# FubarinoMini_v13.net
KiCad netlist of a schematic drawn in EAGLE
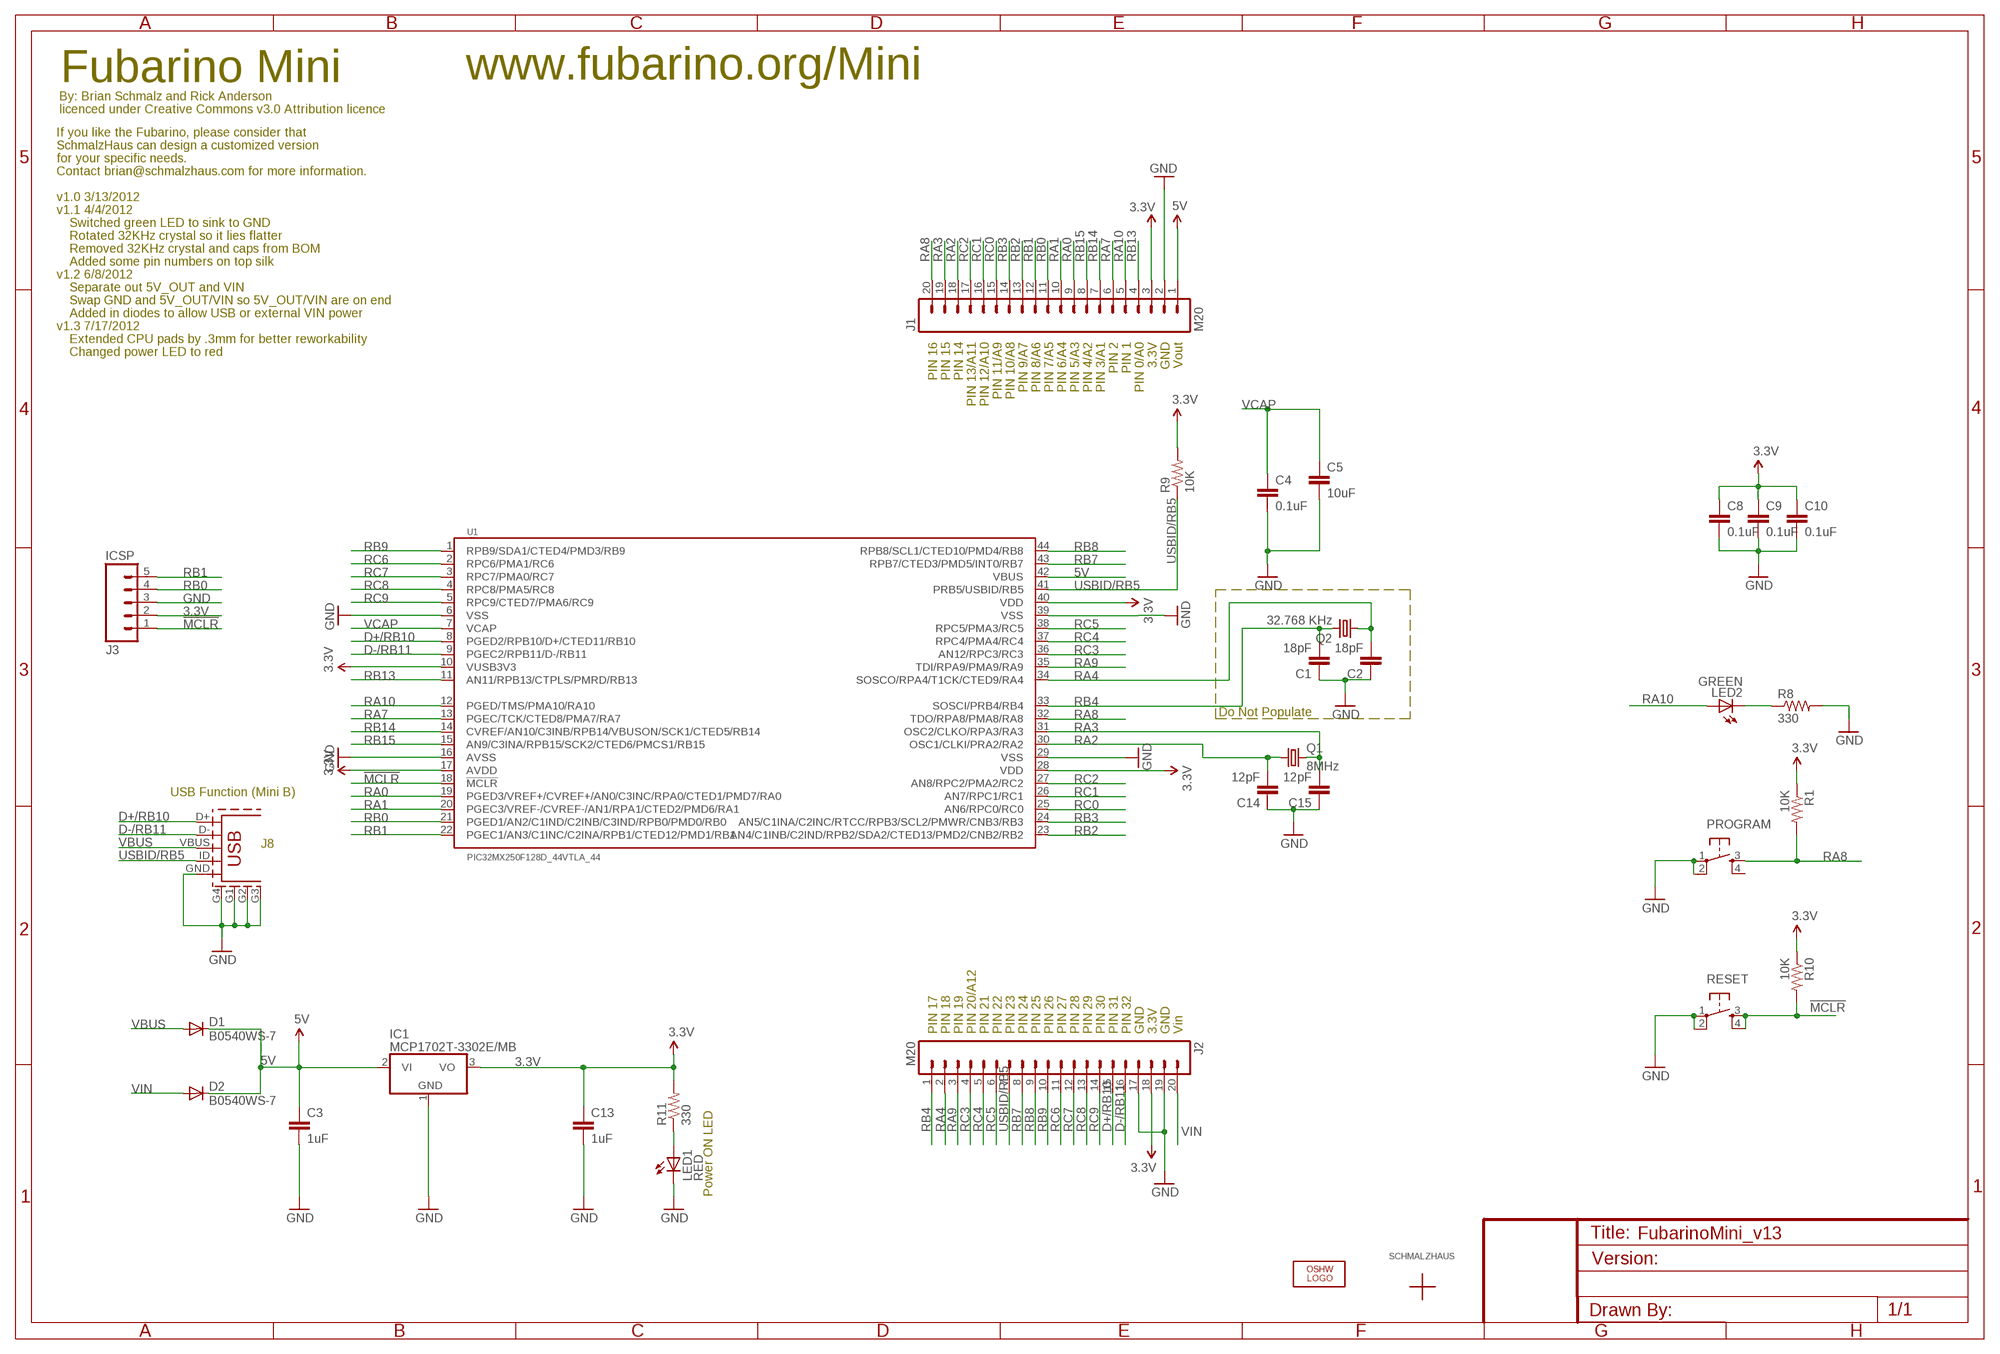
[diagram p0: schematic, sheet 1]

(export (version "E")
  (design (tool "Eeschema 10.0.6"))
  (components
    (comp (ref "C1")
      (value "18pF")
      (footprint "eagle-import:0603-CAP")
      (libsource (lib "eagle-import") (part "SparkFun_CAP0603-CAP"))
    )
    (comp (ref "C2")
      (value "18pF")
      (footprint "eagle-import:0603-CAP")
      (libsource (lib "eagle-import") (part "SparkFun_CAP0603-CAP"))
    )
    (comp (ref "C3")
      (value "1uF")
      (footprint "eagle-import:0603-CAP")
      (libsource (lib "eagle-import") (part "SparkFun_CAP0603-CAP"))
    )
    (comp (ref "C4")
      (value "0.1uF")
      (footprint "eagle-import:0603-CAP")
      (libsource (lib "eagle-import") (part "SparkFun_CAP0603-CAP"))
    )
    (comp (ref "C5")
      (value "10uF")
      (footprint "eagle-import:0805")
      (libsource (lib "eagle-import") (part "CAP0805"))
    )
    (comp (ref "C8")
      (value "0.1uF")
      (footprint "eagle-import:0603-CAP")
      (libsource (lib "eagle-import") (part "SparkFun_CAP0603-CAP"))
    )
    (comp (ref "C9")
      (value "0.1uF")
      (footprint "eagle-import:0603-CAP")
      (libsource (lib "eagle-import") (part "SparkFun_CAP0603-CAP"))
    )
    (comp (ref "C10")
      (value "0.1uF")
      (footprint "eagle-import:0603")
      (libsource (lib "eagle-import") (part "CAP0603"))
    )
    (comp (ref "C13")
      (value "1uF")
      (footprint "eagle-import:0603")
      (libsource (lib "eagle-import") (part "CAP0603"))
    )
    (comp (ref "C14")
      (value "12pF")
      (footprint "eagle-import:0603-CAP")
      (libsource (lib "eagle-import") (part "SparkFun_CAP0603-CAP"))
    )
    (comp (ref "C15")
      (value "12pF")
      (footprint "eagle-import:0603-CAP")
      (libsource (lib "eagle-import") (part "SparkFun_CAP0603-CAP"))
    )
    (comp (ref "D1")
      (value "B0540WS-7")
      (footprint "eagle-import:SOD-323")
      (libsource (lib "eagle-import") (part "DIODESOD"))
    )
    (comp (ref "D2")
      (value "B0540WS-7")
      (footprint "eagle-import:SOD-323")
      (libsource (lib "eagle-import") (part "DIODESOD"))
    )
    (comp (ref "IC1")
      (value "MCP1702T-3302E/MB")
      (footprint "eagle-import:SOT89")
      (libsource (lib "eagle-import") (part "MCP1703MB33"))
    )
    (comp (ref "ICSP")
      (value "J3")
      (footprint "eagle-import:1X05_NOSILK")
      (libsource (lib "eagle-import") (part "M05NOSLILK"))
    )
    (comp (ref "J1")
      (value "M20")
      (footprint "eagle-import:1X20_NO_PIN1")
      (libsource (lib "eagle-import") (part "M20"))
    )
    (comp (ref "J2")
      (value "M20")
      (footprint "eagle-import:1X20_NO_PIN1")
      (libsource (lib "eagle-import") (part "M20"))
    )
    (comp (ref "J8")
      (value "USB_5PIN")
      (footprint "eagle-import:USB-MINIB")
      (libsource (lib "eagle-import") (part "USB_5PIN"))
    )
    (comp (ref "LED1")
      (value "RED")
      (footprint "eagle-import:LED-0603")
      (libsource (lib "eagle-import") (part "LED0603"))
    )
    (comp (ref "LED2")
      (value "GREEN")
      (footprint "eagle-import:LED-0603")
      (libsource (lib "eagle-import") (part "LED0603"))
    )
    (comp (ref "LOGO1")
      (value "OSHW_LOGO_8MILX0070-NT")
      (footprint "eagle-import:OSHW_8X70_NOTEXT")
      (libsource (lib "eagle-import") (part "OSHW_LOGO_8MILX0070-NT"))
    )
    (comp (ref "PROGRAM")
      (value "TAC_SWITCHSND")
      (footprint "eagle-import:TACTILE_SWITCH_SMD")
      (libsource (lib "eagle-import") (part "TAC_SWITCHSND"))
    )
    (comp (ref "Q1")
      (value "8MHz")
      (footprint "eagle-import:NX5032_5MM_3.2MM_CRYSTAL")
      (libsource (lib "eagle-import") (part "CRYSTALNX5032"))
    )
    (comp (ref "Q2")
      (value "32.768 KHz")
      (footprint "eagle-import:TC26H")
      (libsource (lib "eagle-import") (part "CRYSTALTC26H"))
    )
    (comp (ref "R1")
      (value "10K")
      (footprint "eagle-import:0603-RES")
      (libsource (lib "eagle-import") (part "RESISTOR0603-RES"))
    )
    (comp (ref "R8")
      (value "330")
      (footprint "eagle-import:0603-RES")
      (libsource (lib "eagle-import") (part "RESISTOR0603-RES"))
    )
    (comp (ref "R9")
      (value "10K")
      (footprint "eagle-import:0603-RES")
      (libsource (lib "eagle-import") (part "RESISTOR0603-RES"))
    )
    (comp (ref "R10")
      (value "10K")
      (footprint "eagle-import:0603-RES")
      (libsource (lib "eagle-import") (part "RESISTOR0603-RES"))
    )
    (comp (ref "R11")
      (value "330")
      (footprint "eagle-import:0603-RES")
      (libsource (lib "eagle-import") (part "RESISTOR0603-RES"))
    )
    (comp (ref "RESET")
      (value "TAC_SWITCHSND")
      (footprint "eagle-import:TACTILE_SWITCH_SMD")
      (libsource (lib "eagle-import") (part "TAC_SWITCHSND"))
    )
    (comp (ref "U$1")
      (value "SCHMALZHAUSSCHMALZHAUS_SMALL")
      (footprint "eagle-import:SCHMALZHAUS_SMALL")
      (libsource (lib "eagle-import") (part "SCHMALZHAUSSCHMALZHAUS_SMALL"))
    )
    (comp (ref "U1")
      (value "PIC32MX250F128D_44VTLA_44")
      (footprint "eagle-import:VTLA_44")
      (libsource (lib "eagle-import") (part "PIC32MX2XX_44VLA_44"))
    )
  )
  (nets
    (net (code "1") (name "/D+{slash}RB10") (class "Default")
      (node (ref "J2") (pin "15") (pinfunction "15_15") (pintype "passive"))
      (node (ref "J8") (pin "D+") (pinfunction "D+_D+") (pintype "bidirectional"))
      (node (ref "U1") (pin "8") (pinfunction "PGED2/RPB10/D+/CTED11/RB10_8") (pintype "bidirectional"))
    )
    (net (code "2") (name "/D-{slash}RB11") (class "Default")
      (node (ref "J2") (pin "16") (pinfunction "16_16") (pintype "passive"))
      (node (ref "J8") (pin "D-") (pinfunction "D-_D-") (pintype "bidirectional"))
      (node (ref "U1") (pin "9") (pinfunction "PGEC2/RPB11/D-/RB11_9") (pintype "bidirectional"))
    )
    (net (code "3") (name "/RA0") (class "Default")
      (node (ref "J1") (pin "9") (pinfunction "9_9") (pintype "passive"))
      (node (ref "U1") (pin "19") (pinfunction "PGED3/VREF+/CVREF+/AN0/C3INC/RPA0/CTED1/PMD7/RA0_19") (pintype "bidirectional"))
    )
    (net (code "4") (name "/RA1") (class "Default")
      (node (ref "J1") (pin "10") (pinfunction "10_10") (pintype "passive"))
      (node (ref "U1") (pin "20") (pinfunction "PGEC3/VREF-/CVREF-/AN1/RPA1/CTED2/PMD6/RA1_20") (pintype "bidirectional"))
    )
    (net (code "5") (name "/RA2") (class "Default")
      (node (ref "C14") (pin "2") (pinfunction "2_2") (pintype "passive"))
      (node (ref "J1") (pin "18") (pinfunction "18_18") (pintype "passive"))
      (node (ref "Q1") (pin "1") (pinfunction "1_1") (pintype "passive"))
      (node (ref "U1") (pin "30") (pinfunction "OSC1/CLKI/PRA2/RA2_30") (pintype "bidirectional"))
    )
    (net (code "6") (name "/RA3") (class "Default")
      (node (ref "C15") (pin "2") (pinfunction "2_2") (pintype "passive"))
      (node (ref "J1") (pin "19") (pinfunction "19_19") (pintype "passive"))
      (node (ref "Q1") (pin "2") (pinfunction "2_2") (pintype "passive"))
      (node (ref "U1") (pin "31") (pinfunction "OSC2/CLKO/RPA3/RA3_31") (pintype "bidirectional"))
    )
    (net (code "7") (name "/RA4") (class "Default")
      (node (ref "C2") (pin "2") (pinfunction "2_2") (pintype "passive"))
      (node (ref "J2") (pin "2") (pinfunction "2_2") (pintype "passive"))
      (node (ref "Q2") (pin "1") (pinfunction "1_1") (pintype "passive"))
      (node (ref "U1") (pin "34") (pinfunction "SOSCO/RPA4/T1CK/CTED9/RA4_34") (pintype "bidirectional"))
    )
    (net (code "8") (name "/RA7") (class "Default")
      (node (ref "J1") (pin "6") (pinfunction "6_6") (pintype "passive"))
      (node (ref "U1") (pin "13") (pinfunction "PGEC/TCK/CTED8/PMA7/RA7_13") (pintype "bidirectional"))
    )
    (net (code "9") (name "/RA8") (class "Default")
      (node (ref "J1") (pin "20") (pinfunction "20_20") (pintype "passive"))
      (node (ref "PROGRAM") (pin "3") (pinfunction "3_3") (pintype "passive"))
      (node (ref "R1") (pin "2") (pinfunction "2_2") (pintype "passive"))
      (node (ref "U1") (pin "32") (pinfunction "TDO/RPA8/PMA8/RA8_32") (pintype "bidirectional"))
    )
    (net (code "10") (name "/RA9") (class "Default")
      (node (ref "J2") (pin "3") (pinfunction "3_3") (pintype "passive"))
      (node (ref "U1") (pin "35") (pinfunction "TDI/RPA9/PMA9/RA9_35") (pintype "bidirectional"))
    )
    (net (code "11") (name "/RA10") (class "Default")
      (node (ref "J1") (pin "5") (pinfunction "5_5") (pintype "passive"))
      (node (ref "LED2") (pin "A") (pinfunction "A_A") (pintype "passive"))
      (node (ref "U1") (pin "12") (pinfunction "PGED/TMS/PMA10/RA10_12") (pintype "bidirectional"))
    )
    (net (code "12") (name "/RB0") (class "Default")
      (node (ref "ICSP") (pin "4") (pinfunction "4_4") (pintype "passive"))
      (node (ref "J1") (pin "11") (pinfunction "11_11") (pintype "passive"))
      (node (ref "U1") (pin "21") (pinfunction "PGED1/AN2/C1IND/C2INB/C3IND/RPB0/PMD0/RB0_21") (pintype "bidirectional"))
    )
    (net (code "13") (name "/RB1") (class "Default")
      (node (ref "ICSP") (pin "5") (pinfunction "5_5") (pintype "passive"))
      (node (ref "J1") (pin "12") (pinfunction "12_12") (pintype "passive"))
      (node (ref "U1") (pin "22") (pinfunction "PGEC1/AN3/C1INC/C2INA/RPB1/CTED12/PMD1/RB1_22") (pintype "bidirectional"))
    )
    (net (code "14") (name "/RB2") (class "Default")
      (node (ref "J1") (pin "13") (pinfunction "13_13") (pintype "passive"))
      (node (ref "U1") (pin "23") (pinfunction "AN4/C1INB/C2IND/RPB2/SDA2/CTED13/PMD2/CNB2/RB2_23") (pintype "bidirectional"))
    )
    (net (code "15") (name "/RB3") (class "Default")
      (node (ref "J1") (pin "14") (pinfunction "14_14") (pintype "passive"))
      (node (ref "U1") (pin "24") (pinfunction "AN5/C1INA/C2INC/RTCC/RPB3/SCL2/PMWR/CNB3/RB3_24") (pintype "bidirectional"))
    )
    (net (code "16") (name "/RB4") (class "Default")
      (node (ref "C1") (pin "2") (pinfunction "2_2") (pintype "passive"))
      (node (ref "J2") (pin "1") (pinfunction "1_1") (pintype "passive"))
      (node (ref "Q2") (pin "2") (pinfunction "2_2") (pintype "passive"))
      (node (ref "U1") (pin "33") (pinfunction "SOSCI/PRB4/RB4_33") (pintype "bidirectional"))
    )
    (net (code "17") (name "/RB7") (class "Default")
      (node (ref "J2") (pin "8") (pinfunction "8_8") (pintype "passive"))
      (node (ref "U1") (pin "43") (pinfunction "RPB7/CTED3/PMD5/INT0/RB7_43") (pintype "bidirectional"))
    )
    (net (code "18") (name "/RB8") (class "Default")
      (node (ref "J2") (pin "9") (pinfunction "9_9") (pintype "passive"))
      (node (ref "U1") (pin "44") (pinfunction "RPB8/SCL1/CTED10/PMD4/RB8_44") (pintype "bidirectional"))
    )
    (net (code "19") (name "/RB9") (class "Default")
      (node (ref "J2") (pin "10") (pinfunction "10_10") (pintype "passive"))
      (node (ref "U1") (pin "1") (pinfunction "RPB9/SDA1/CTED4/PMD3/RB9_1") (pintype "bidirectional"))
    )
    (net (code "20") (name "/RB13") (class "Default")
      (node (ref "J1") (pin "4") (pinfunction "4_4") (pintype "passive"))
      (node (ref "U1") (pin "11") (pinfunction "AN11/RPB13/CTPLS/PMRD/RB13_11") (pintype "bidirectional"))
    )
    (net (code "21") (name "/RB14") (class "Default")
      (node (ref "J1") (pin "7") (pinfunction "7_7") (pintype "passive"))
      (node (ref "U1") (pin "14") (pinfunction "CVREF/AN10/C3INB/RPB14/VBUSON/SCK1/CTED5/RB14_14") (pintype "bidirectional"))
    )
    (net (code "22") (name "/RB15") (class "Default")
      (node (ref "J1") (pin "8") (pinfunction "8_8") (pintype "passive"))
      (node (ref "U1") (pin "15") (pinfunction "AN9/C3INA/RPB15/SCK2/CTED6/PMCS1/RB15_15") (pintype "bidirectional"))
    )
    (net (code "23") (name "/RC0") (class "Default")
      (node (ref "J1") (pin "15") (pinfunction "15_15") (pintype "passive"))
      (node (ref "U1") (pin "25") (pinfunction "AN6/RPC0/RC0_25") (pintype "bidirectional"))
    )
    (net (code "24") (name "/RC1") (class "Default")
      (node (ref "J1") (pin "16") (pinfunction "16_16") (pintype "passive"))
      (node (ref "U1") (pin "26") (pinfunction "AN7/RPC1/RC1_26") (pintype "bidirectional"))
    )
    (net (code "25") (name "/RC2") (class "Default")
      (node (ref "J1") (pin "17") (pinfunction "17_17") (pintype "passive"))
      (node (ref "U1") (pin "27") (pinfunction "AN8/RPC2/PMA2/RC2_27") (pintype "bidirectional"))
    )
    (net (code "26") (name "/RC3") (class "Default")
      (node (ref "J2") (pin "4") (pinfunction "4_4") (pintype "passive"))
      (node (ref "U1") (pin "36") (pinfunction "AN12/RPC3/RC3_36") (pintype "bidirectional"))
    )
    (net (code "27") (name "/RC4") (class "Default")
      (node (ref "J2") (pin "5") (pinfunction "5_5") (pintype "passive"))
      (node (ref "U1") (pin "37") (pinfunction "RPC4/PMA4/RC4_37") (pintype "bidirectional"))
    )
    (net (code "28") (name "/RC5") (class "Default")
      (node (ref "J2") (pin "6") (pinfunction "6_6") (pintype "passive"))
      (node (ref "U1") (pin "38") (pinfunction "RPC5/PMA3/RC5_38") (pintype "bidirectional"))
    )
    (net (code "29") (name "/RC6") (class "Default")
      (node (ref "J2") (pin "11") (pinfunction "11_11") (pintype "passive"))
      (node (ref "U1") (pin "2") (pinfunction "RPC6/PMA1/RC6_2") (pintype "bidirectional"))
    )
    (net (code "30") (name "/RC7") (class "Default")
      (node (ref "J2") (pin "12") (pinfunction "12_12") (pintype "passive"))
      (node (ref "U1") (pin "3") (pinfunction "RPC7/PMA0/RC7_3") (pintype "bidirectional"))
    )
    (net (code "31") (name "/RC8") (class "Default")
      (node (ref "J2") (pin "13") (pinfunction "13_13") (pintype "passive"))
      (node (ref "U1") (pin "4") (pinfunction "RPC8/PMA5/RC8_4") (pintype "bidirectional"))
    )
    (net (code "32") (name "/RC9") (class "Default")
      (node (ref "J2") (pin "14") (pinfunction "14_14") (pintype "passive"))
      (node (ref "U1") (pin "5") (pinfunction "RPC9/CTED7/PMA6/RC9_5") (pintype "bidirectional"))
    )
    (net (code "33") (name "/USBID{slash}RB5") (class "Default")
      (node (ref "J2") (pin "7") (pinfunction "7_7") (pintype "passive"))
      (node (ref "J8") (pin "ID") (pinfunction "USB_ID_ID") (pintype "bidirectional"))
      (node (ref "R9") (pin "1") (pinfunction "1_1") (pintype "passive"))
      (node (ref "U1") (pin "41") (pinfunction "PRB5/USBID/RB5_41") (pintype "bidirectional"))
    )
    (net (code "34") (name "/VBUS") (class "Default")
      (node (ref "D1") (pin "2") (pinfunction "A_2") (pintype "passive"))
      (node (ref "J8") (pin "VBUS") (pinfunction "VBUS_VBUS") (pintype "bidirectional"))
    )
    (net (code "35") (name "/VCAP") (class "Default")
      (node (ref "C4") (pin "1") (pinfunction "1_1") (pintype "passive"))
      (node (ref "C5") (pin "1") (pinfunction "1_1") (pintype "passive"))
      (node (ref "U1") (pin "7") (pinfunction "VCAP_7") (pintype "bidirectional"))
    )
    (net (code "36") (name "/VIN") (class "Default")
      (node (ref "D2") (pin "2") (pinfunction "A_2") (pintype "passive"))
      (node (ref "J2") (pin "20") (pinfunction "20_20") (pintype "passive"))
    )
    (net (code "37") (name "/~{MCLR}") (class "Default")
      (node (ref "ICSP") (pin "1") (pinfunction "1_1") (pintype "passive"))
      (node (ref "R10") (pin "2") (pinfunction "2_2") (pintype "passive"))
      (node (ref "RESET") (pin "3") (pinfunction "3_3") (pintype "passive"))
      (node (ref "RESET") (pin "4") (pinfunction "4_4") (pintype "passive"))
      (node (ref "U1") (pin "18") (pinfunction "~{MCLR}_18") (pintype "bidirectional"))
    )
    (net (code "38") (name "3.3V") (class "Default")
      (node (ref "C10") (pin "1") (pinfunction "1_1") (pintype "passive"))
      (node (ref "C13") (pin "1") (pinfunction "1_1") (pintype "passive"))
      (node (ref "C8") (pin "1") (pinfunction "1_1") (pintype "passive"))
      (node (ref "C9") (pin "1") (pinfunction "1_1") (pintype "passive"))
      (node (ref "IC1") (pin "3") (pinfunction "VO_3") (pintype "passive"))
      (node (ref "ICSP") (pin "2") (pinfunction "2_2") (pintype "passive"))
      (node (ref "J1") (pin "3") (pinfunction "3_3") (pintype "passive"))
      (node (ref "J2") (pin "18") (pinfunction "18_18") (pintype "passive"))
      (node (ref "R1") (pin "1") (pinfunction "1_1") (pintype "passive"))
      (node (ref "R10") (pin "1") (pinfunction "1_1") (pintype "passive"))
      (node (ref "R11") (pin "2") (pinfunction "2_2") (pintype "passive"))
      (node (ref "R9") (pin "2") (pinfunction "2_2") (pintype "passive"))
      (node (ref "U1") (pin "10") (pinfunction "VUSB3V3_10") (pintype "bidirectional"))
      (node (ref "U1") (pin "17") (pinfunction "AVDD_17") (pintype "bidirectional"))
      (node (ref "U1") (pin "28") (pinfunction "VDD_28") (pintype "bidirectional"))
      (node (ref "U1") (pin "40") (pinfunction "VDD_40") (pintype "bidirectional"))
    )
    (net (code "39") (name "5V") (class "Default")
      (node (ref "C3") (pin "1") (pinfunction "1_1") (pintype "passive"))
      (node (ref "D1") (pin "1") (pinfunction "C_1") (pintype "passive"))
      (node (ref "D2") (pin "1") (pinfunction "C_1") (pintype "passive"))
      (node (ref "IC1") (pin "2") (pinfunction "VI_2") (pintype "input"))
      (node (ref "IC1") (pin "2@1") (pinfunction "VI1_2@1") (pintype "input"))
      (node (ref "J1") (pin "1") (pinfunction "1_1") (pintype "passive"))
      (node (ref "U1") (pin "42") (pinfunction "VBUS_42") (pintype "bidirectional"))
    )
    (net (code "40") (name "GND") (class "Default")
      (node (ref "C1") (pin "1") (pinfunction "1_1") (pintype "passive"))
      (node (ref "C10") (pin "2") (pinfunction "2_2") (pintype "passive"))
      (node (ref "C13") (pin "2") (pinfunction "2_2") (pintype "passive"))
      (node (ref "C14") (pin "1") (pinfunction "1_1") (pintype "passive"))
      (node (ref "C15") (pin "1") (pinfunction "1_1") (pintype "passive"))
      (node (ref "C2") (pin "1") (pinfunction "1_1") (pintype "passive"))
      (node (ref "C3") (pin "2") (pinfunction "2_2") (pintype "passive"))
      (node (ref "C4") (pin "2") (pinfunction "2_2") (pintype "passive"))
      (node (ref "C5") (pin "2") (pinfunction "2_2") (pintype "passive"))
      (node (ref "C8") (pin "2") (pinfunction "2_2") (pintype "passive"))
      (node (ref "C9") (pin "2") (pinfunction "2_2") (pintype "passive"))
      (node (ref "IC1") (pin "1") (pinfunction "GND_1") (pintype "passive"))
      (node (ref "ICSP") (pin "3") (pinfunction "3_3") (pintype "passive"))
      (node (ref "J1") (pin "2") (pinfunction "2_2") (pintype "passive"))
      (node (ref "J2") (pin "17") (pinfunction "17_17") (pintype "passive"))
      (node (ref "J2") (pin "19") (pinfunction "19_19") (pintype "passive"))
      (node (ref "J8") (pin "G1") (pinfunction "P$1_G1") (pintype "bidirectional"))
      (node (ref "J8") (pin "G2") (pinfunction "P$2_G2") (pintype "bidirectional"))
      (node (ref "J8") (pin "G3") (pinfunction "P$3_G3") (pintype "bidirectional"))
      (node (ref "J8") (pin "G4") (pinfunction "SHIELD_G4") (pintype "bidirectional"))
      (node (ref "J8") (pin "GND") (pinfunction "GND_GND") (pintype "bidirectional"))
      (node (ref "LED1") (pin "C") (pinfunction "C_C") (pintype "passive"))
      (node (ref "PROGRAM") (pin "1") (pinfunction "1_1") (pintype "passive"))
      (node (ref "PROGRAM") (pin "2") (pinfunction "2_2") (pintype "passive"))
      (node (ref "R8") (pin "2") (pinfunction "2_2") (pintype "passive"))
      (node (ref "RESET") (pin "1") (pinfunction "1_1") (pintype "passive"))
      (node (ref "RESET") (pin "2") (pinfunction "2_2") (pintype "passive"))
      (node (ref "U1") (pin "16") (pinfunction "AVSS_16") (pintype "bidirectional"))
      (node (ref "U1") (pin "29") (pinfunction "VSS_29") (pintype "bidirectional"))
      (node (ref "U1") (pin "39") (pinfunction "VSS_39") (pintype "bidirectional"))
      (node (ref "U1") (pin "6") (pinfunction "VSS_6") (pintype "bidirectional"))
    )
    (net (code "41") (name "Net-(LED1-PadA)") (class "Default")
      (node (ref "LED1") (pin "A") (pinfunction "A_A") (pintype "passive"))
      (node (ref "R11") (pin "1") (pinfunction "1_1") (pintype "passive"))
    )
    (net (code "42") (name "Net-(LED2-PadC)") (class "Default")
      (node (ref "LED2") (pin "C") (pinfunction "C_C") (pintype "passive"))
      (node (ref "R8") (pin "1") (pinfunction "1_1") (pintype "passive"))
    )
    (net (code "43") (name "unconnected-(PROGRAM-Pad4)") (class "Default")
      (node (ref "PROGRAM") (pin "4") (pinfunction "4_4") (pintype "passive"))
    )
  )
)
